# SCH_PID_LINE_FOLLOWER_2023-06-07.net
KiCad netlist of a schematic drawn in EasyEDA
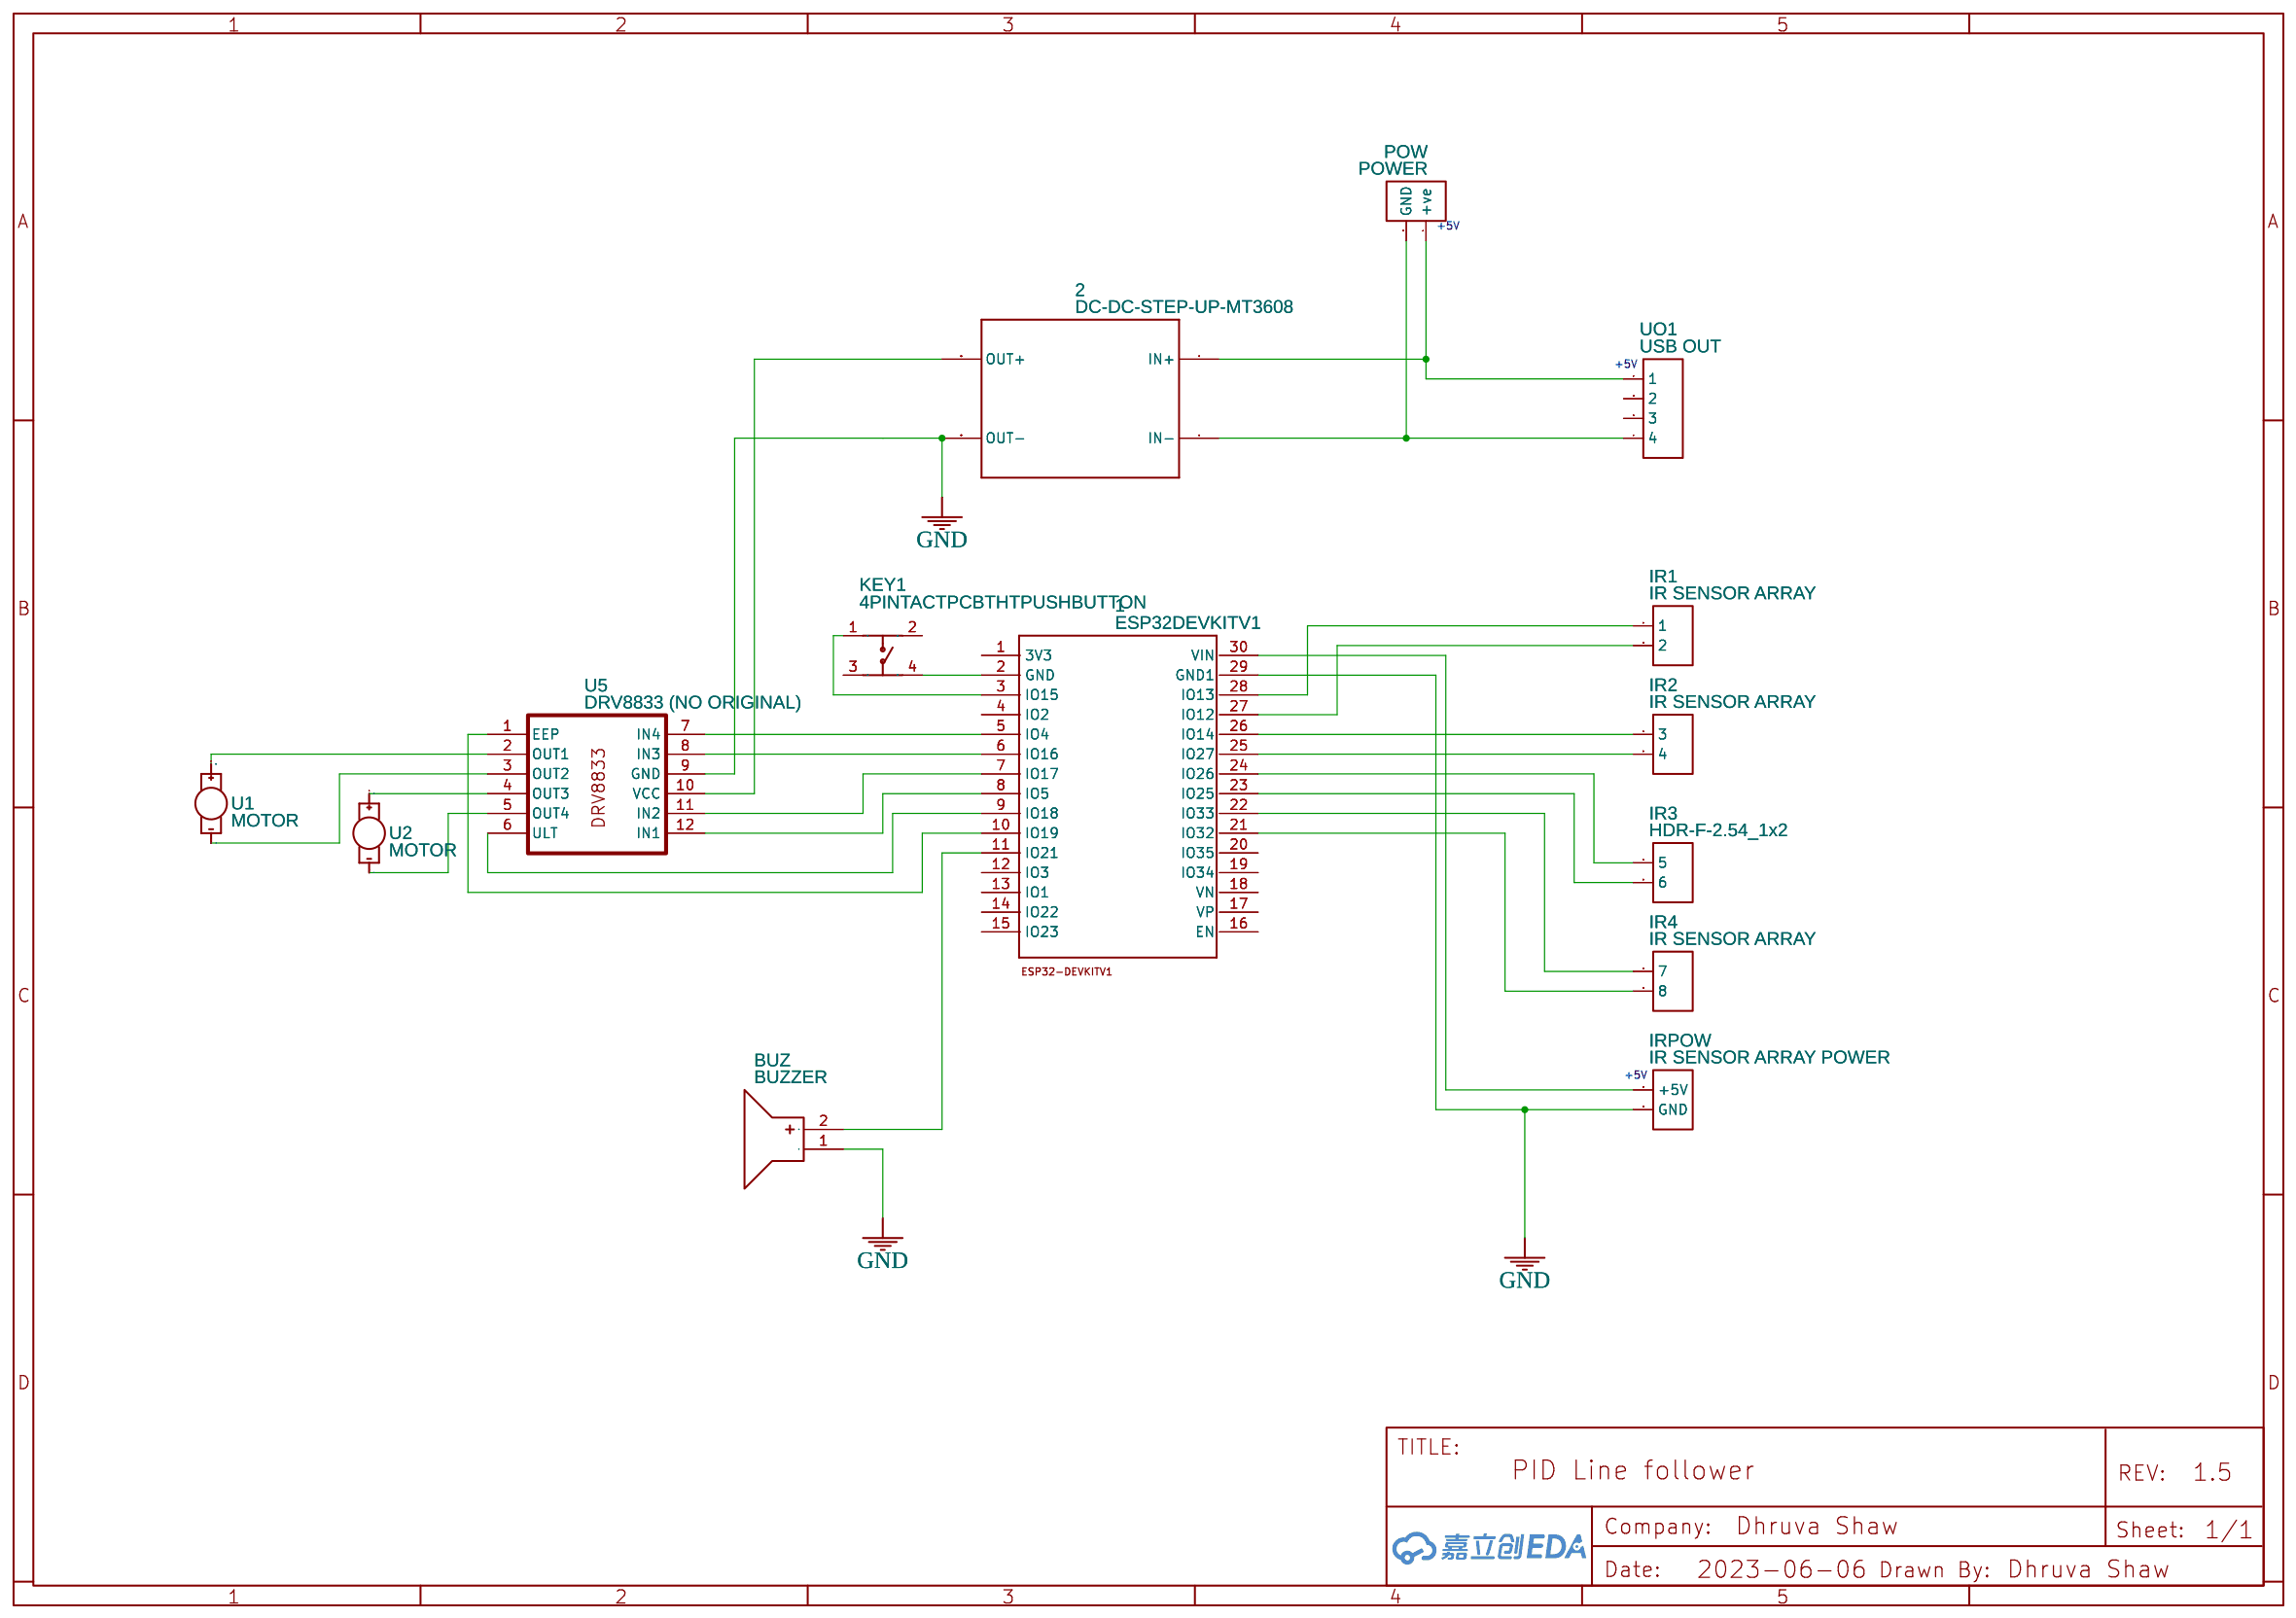
[diagram p0: schematic sheet]

(export (version "E")
  (design (tool "Eeschema 10.0.6"))
  (components
    (comp (ref "1") (value "ESP32DEVKITV1") (libsource (lib "") (part "ESP32DEVKITV1")))
    (comp (ref "2") (value "DC-DC-STEP-UP-MT3608") (libsource (lib "") (part "DC-DC-STEP-UP-MT3608")))
    (comp (ref "BUZ")
      (value "BUZZER")
      (fields
        (field (name "BOM_Manufacturer Part") "buzzer")
        (field (name "BOM_Supplier Part") "C9900014030")
      )
      (libsource (lib "") (part "BUZZER"))
    )
    (comp (ref "IR1")
      (value "IR SENSOR ARRAY")
      (fields (field (name "BOM_Supplier Part") "C49661"))
      (libsource (lib "") (part "HDR-F-2.54_1x2"))
    )
    (comp (ref "IR2")
      (value "IR SENSOR ARRAY")
      (fields (field (name "BOM_Supplier Part") "C49661"))
      (libsource (lib "") (part "HDR-F-2.54_1x2_4"))
    )
    (comp (ref "IR3")
      (value "HDR-F-2.54_1x2")
      (fields (field (name "BOM_Supplier Part") "C49661"))
      (libsource (lib "") (part "HDR-F-2.54_1x2_1"))
    )
    (comp (ref "IR4")
      (value "IR SENSOR ARRAY")
      (fields (field (name "BOM_Supplier Part") "C49661"))
      (libsource (lib "") (part "HDR-F-2.54_1x2_2"))
    )
    (comp (ref "IRPOW")
      (value "IR SENSOR ARRAY POWER")
      (fields (field (name "BOM_Supplier Part") "C49661"))
      (libsource (lib "") (part "HDR-F-2.54_1x2_3"))
    )
    (comp (ref "KEY1")
      (value "4PINTACTPCBTHTPUSHBUTTON")
      (fields
        (field (name "BOM_Manufacturer Part") "4pinTACTPCBTHTPushButton")
        (field (name "BOM_Supplier Part") "C9900003768")
      )
      (libsource (lib "") (part "4PINTACTPCBTHTPUSHBUTTON"))
    )
    (comp (ref "POW")
      (value "POWER")
      (fields (field (name "BOM_Supplier Part") "C49661"))
      (libsource (lib "") (part "HDR-F-2.54_1x2_5"))
    )
    (comp (ref "U1") (value "MOTOR") (libsource (lib "") (part "MOTOR")))
    (comp (ref "U2") (value "MOTOR") (libsource (lib "") (part "MOTOR")))
    (comp (ref "U5") (value "DRV8833 (NO ORIGINAL)") (libsource (lib "") (part "DRV8833 (NO ORIGINAL)")))
    (comp (ref "UO1")
      (value "USB OUT")
      (fields (field (name "BOM_Supplier Part") "C225501"))
      (libsource (lib "") (part "HDR-F-2.54_1x4"))
    )
  )
  (nets
    (net (code "1") (name "GND") (class "Default")
      (node (ref "1") (pin "29") (pinfunction "GND1_29") (pintype "bidirectional"))
      (node (ref "2") (pin "OUT-") (pinfunction "OUT-_OUT-") (pintype "bidirectional"))
      (node (ref "BUZ") (pin "1") (pinfunction "-_1") (pintype "unspecified"))
      (node (ref "IRPOW") (pin "2") (pinfunction "GND_2") (pintype "input"))
      (node (ref "U5") (pin "9") (pinfunction "GND_9") (pintype "unspecified"))
    )
    (net (code "2") (name "Net-(1-GND)") (class "Default")
      (node (ref "1") (pin "2") (pinfunction "GND_2") (pintype "bidirectional"))
      (node (ref "KEY1") (pin "4") (pinfunction "4_4") (pintype "unspecified"))
    )
    (net (code "3") (name "Net-(1-IO4)") (class "Default")
      (node (ref "1") (pin "5") (pinfunction "IO4_5") (pintype "bidirectional"))
      (node (ref "U5") (pin "7") (pinfunction "IN4_7") (pintype "unspecified"))
    )
    (net (code "4") (name "Net-(1-IO5)") (class "Default")
      (node (ref "1") (pin "8") (pinfunction "IO5_8") (pintype "bidirectional"))
      (node (ref "U5") (pin "12") (pinfunction "IN1_12") (pintype "unspecified"))
    )
    (net (code "5") (name "Net-(1-IO12)") (class "Default")
      (node (ref "1") (pin "27") (pinfunction "IO12_27") (pintype "bidirectional"))
      (node (ref "IR1") (pin "2") (pinfunction "2_2") (pintype "input"))
    )
    (net (code "6") (name "Net-(1-IO13)") (class "Default")
      (node (ref "1") (pin "28") (pinfunction "IO13_28") (pintype "bidirectional"))
      (node (ref "IR1") (pin "1") (pinfunction "1_1") (pintype "input"))
    )
    (net (code "7") (name "Net-(1-IO14)") (class "Default")
      (node (ref "1") (pin "26") (pinfunction "IO14_26") (pintype "bidirectional"))
      (node (ref "IR2") (pin "1") (pinfunction "3_1") (pintype "input"))
    )
    (net (code "8") (name "Net-(1-IO15)") (class "Default")
      (node (ref "1") (pin "3") (pinfunction "IO15_3") (pintype "bidirectional"))
      (node (ref "KEY1") (pin "1") (pinfunction "1_1") (pintype "unspecified"))
    )
    (net (code "9") (name "Net-(1-IO16)") (class "Default")
      (node (ref "1") (pin "6") (pinfunction "IO16_6") (pintype "bidirectional"))
      (node (ref "U5") (pin "8") (pinfunction "IN3_8") (pintype "unspecified"))
    )
    (net (code "10") (name "Net-(1-IO17)") (class "Default")
      (node (ref "1") (pin "7") (pinfunction "IO17_7") (pintype "bidirectional"))
      (node (ref "U5") (pin "11") (pinfunction "IN2_11") (pintype "unspecified"))
    )
    (net (code "11") (name "Net-(1-IO18)") (class "Default")
      (node (ref "1") (pin "9") (pinfunction "IO18_9") (pintype "bidirectional"))
      (node (ref "U5") (pin "6") (pinfunction "ULT_6") (pintype "unspecified"))
    )
    (net (code "12") (name "Net-(1-IO19)") (class "Default")
      (node (ref "1") (pin "10") (pinfunction "IO19_10") (pintype "bidirectional"))
      (node (ref "U5") (pin "1") (pinfunction "EEP_1") (pintype "unspecified"))
    )
    (net (code "13") (name "Net-(1-IO21)") (class "Default")
      (node (ref "1") (pin "11") (pinfunction "IO21_11") (pintype "bidirectional"))
      (node (ref "BUZ") (pin "2") (pinfunction "+_2") (pintype "unspecified"))
    )
    (net (code "14") (name "Net-(1-IO25)") (class "Default")
      (node (ref "1") (pin "23") (pinfunction "IO25_23") (pintype "bidirectional"))
      (node (ref "IR3") (pin "2") (pinfunction "6_2") (pintype "input"))
    )
    (net (code "15") (name "Net-(1-IO26)") (class "Default")
      (node (ref "1") (pin "24") (pinfunction "IO26_24") (pintype "bidirectional"))
      (node (ref "IR3") (pin "1") (pinfunction "5_1") (pintype "input"))
    )
    (net (code "16") (name "Net-(1-IO27)") (class "Default")
      (node (ref "1") (pin "25") (pinfunction "IO27_25") (pintype "bidirectional"))
      (node (ref "IR2") (pin "2") (pinfunction "4_2") (pintype "input"))
    )
    (net (code "17") (name "Net-(1-IO32)") (class "Default")
      (node (ref "1") (pin "21") (pinfunction "IO32_21") (pintype "bidirectional"))
      (node (ref "IR4") (pin "2") (pinfunction "8_2") (pintype "input"))
    )
    (net (code "18") (name "Net-(1-IO33)") (class "Default")
      (node (ref "1") (pin "22") (pinfunction "IO33_22") (pintype "bidirectional"))
      (node (ref "IR4") (pin "1") (pinfunction "7_1") (pintype "input"))
    )
    (net (code "19") (name "Net-(1-VIN)") (class "Default")
      (node (ref "1") (pin "30") (pinfunction "VIN_30") (pintype "bidirectional"))
      (node (ref "IRPOW") (pin "1") (pinfunction "+5V_1") (pintype "input"))
    )
    (net (code "20") (name "Net-(POW-+ve)") (class "Default")
      (node (ref "2") (pin "IN+") (pinfunction "IN+_IN+") (pintype "bidirectional"))
      (node (ref "POW") (pin "1") (pinfunction "+ve_1") (pintype "input"))
      (node (ref "UO1") (pin "1") (pinfunction "1_1") (pintype "unspecified"))
    )
    (net (code "21") (name "Net-(POW-GND)") (class "Default")
      (node (ref "2") (pin "IN-") (pinfunction "IN-_IN-") (pintype "bidirectional"))
      (node (ref "POW") (pin "2") (pinfunction "GND_2") (pintype "input"))
      (node (ref "UO1") (pin "4") (pinfunction "4_4") (pintype "unspecified"))
    )
    (net (code "22") (name "Net-(U5-OUT1)") (class "Default")
      (node (ref "U1") (pin "+") (pinfunction "+_+") (pintype "unspecified"))
      (node (ref "U5") (pin "2") (pinfunction "OUT1_2") (pintype "unspecified"))
    )
    (net (code "23") (name "Net-(U5-OUT2)") (class "Default")
      (node (ref "U1") (pin "-") (pinfunction "-_-") (pintype "unspecified"))
      (node (ref "U5") (pin "3") (pinfunction "OUT2_3") (pintype "unspecified"))
    )
    (net (code "24") (name "Net-(U5-OUT3)") (class "Default")
      (node (ref "U2") (pin "+") (pinfunction "+_+") (pintype "unspecified"))
      (node (ref "U5") (pin "4") (pinfunction "OUT3_4") (pintype "unspecified"))
    )
    (net (code "25") (name "Net-(U5-OUT4)") (class "Default")
      (node (ref "U2") (pin "-") (pinfunction "-_-") (pintype "unspecified"))
      (node (ref "U5") (pin "5") (pinfunction "OUT4_5") (pintype "unspecified"))
    )
    (net (code "26") (name "Net-(U5-VCC)") (class "Default")
      (node (ref "2") (pin "OUT+") (pinfunction "OUT+_OUT+") (pintype "bidirectional"))
      (node (ref "U5") (pin "10") (pinfunction "VCC_10") (pintype "unspecified"))
    )
    (net (code "27") (name "unconnected-(1-3V3-Pad1)") (class "Default")
      (node (ref "1") (pin "1") (pinfunction "3V3_1") (pintype "bidirectional"))
    )
    (net (code "28") (name "unconnected-(1-EN-Pad16)") (class "Default")
      (node (ref "1") (pin "16") (pinfunction "EN_16") (pintype "bidirectional"))
    )
    (net (code "29") (name "unconnected-(1-IO1-Pad13)") (class "Default")
      (node (ref "1") (pin "13") (pinfunction "IO1_13") (pintype "bidirectional"))
    )
    (net (code "30") (name "unconnected-(1-IO2-Pad4)") (class "Default")
      (node (ref "1") (pin "4") (pinfunction "IO2_4") (pintype "bidirectional"))
    )
    (net (code "31") (name "unconnected-(1-IO3-Pad12)") (class "Default")
      (node (ref "1") (pin "12") (pinfunction "IO3_12") (pintype "bidirectional"))
    )
    (net (code "32") (name "unconnected-(1-IO22-Pad14)") (class "Default")
      (node (ref "1") (pin "14") (pinfunction "IO22_14") (pintype "bidirectional"))
    )
    (net (code "33") (name "unconnected-(1-IO23-Pad15)") (class "Default")
      (node (ref "1") (pin "15") (pinfunction "IO23_15") (pintype "bidirectional"))
    )
    (net (code "34") (name "unconnected-(1-IO34-Pad19)") (class "Default")
      (node (ref "1") (pin "19") (pinfunction "IO34_19") (pintype "bidirectional"))
    )
    (net (code "35") (name "unconnected-(1-IO35-Pad20)") (class "Default")
      (node (ref "1") (pin "20") (pinfunction "IO35_20") (pintype "bidirectional"))
    )
    (net (code "36") (name "unconnected-(1-VN-Pad18)") (class "Default")
      (node (ref "1") (pin "18") (pinfunction "VN_18") (pintype "bidirectional"))
    )
    (net (code "37") (name "unconnected-(1-VP-Pad17)") (class "Default")
      (node (ref "1") (pin "17") (pinfunction "VP_17") (pintype "bidirectional"))
    )
    (net (code "38") (name "unconnected-(KEY1-Pad2)") (class "Default")
      (node (ref "KEY1") (pin "2") (pinfunction "2_2") (pintype "unspecified"))
    )
    (net (code "39") (name "unconnected-(KEY1-Pad3)") (class "Default")
      (node (ref "KEY1") (pin "3") (pinfunction "3_3") (pintype "unspecified"))
    )
    (net (code "40") (name "unconnected-(UO1-Pad2)") (class "Default")
      (node (ref "UO1") (pin "2") (pinfunction "2_2") (pintype "unspecified"))
    )
    (net (code "41") (name "unconnected-(UO1-Pad3)") (class "Default")
      (node (ref "UO1") (pin "3") (pinfunction "3_3") (pintype "unspecified"))
    )
  )
)
